# SCH_-_Peripheral.net
KiCad netlist of a schematic drawn in Altium Designer
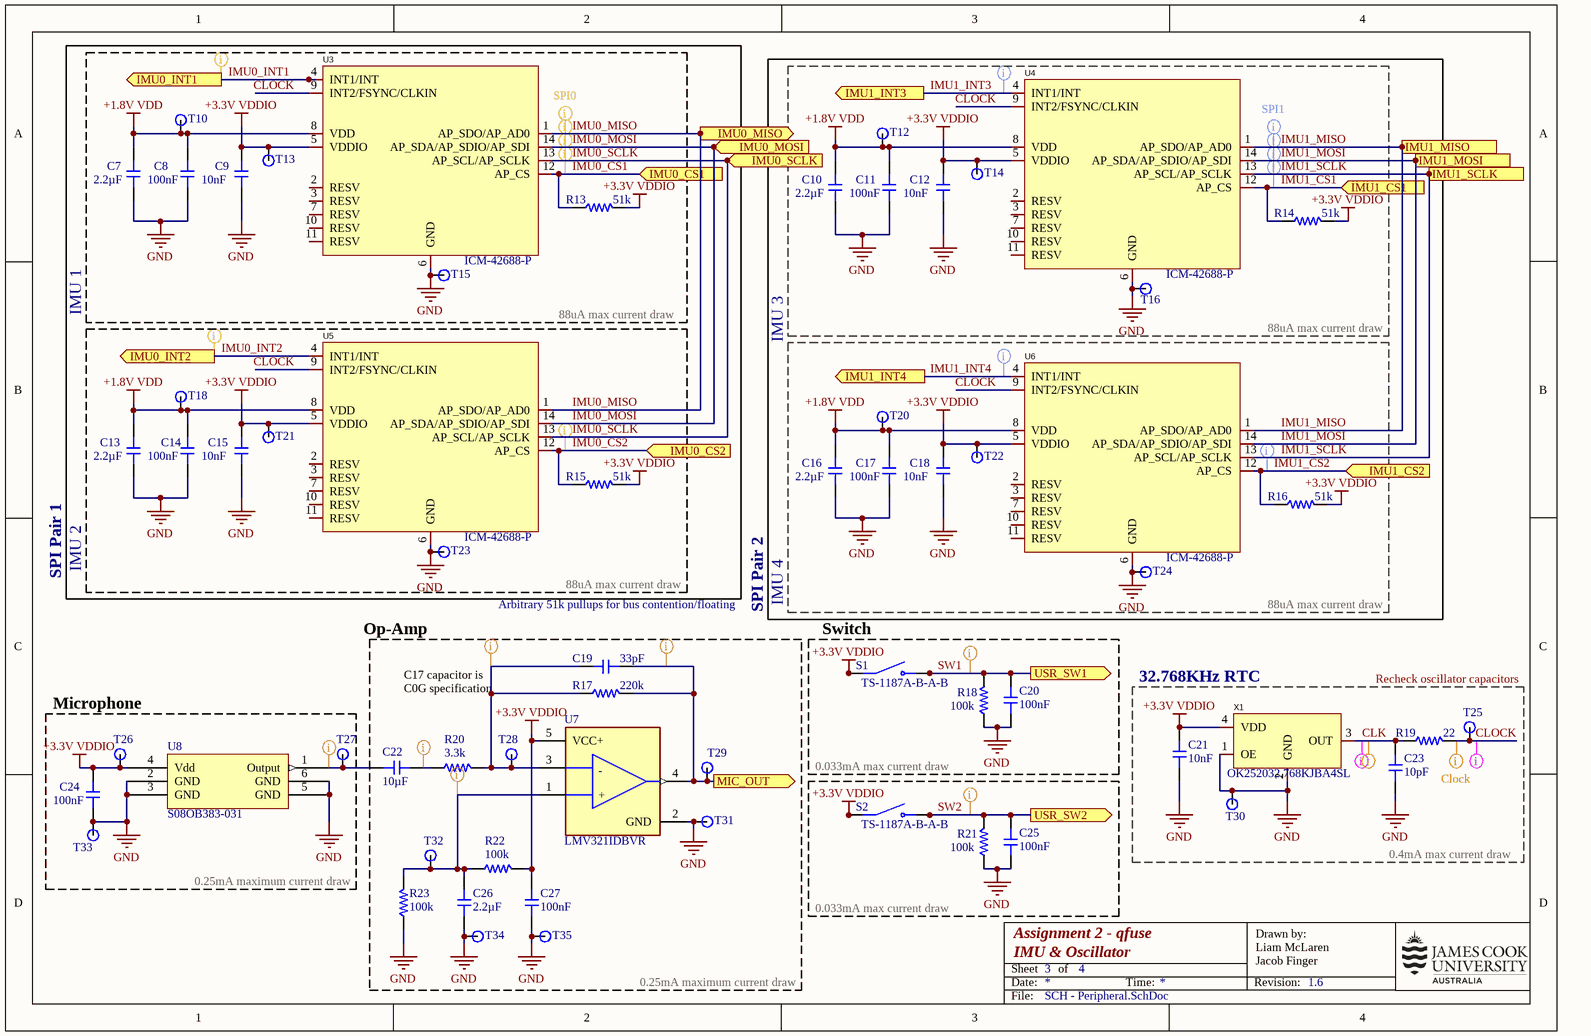
[diagram p0: SCH - Peripheral.SchDoc]

(export (version "E")
  (design (tool "Eeschema 10.0.6"))
  (components
    (comp (ref "C7")
      (value "2.2µF")
      (footprint "CAP-0402")
      (description "Capacitor, Ceramic (MLCC), 2.2uF, ±20%, 6.3V, X5R, ±20%, SMD 0402")
      (fields (field (name "TOLERANCE") "20%") (field (name "JLCPCB PART NUMBER") "C12530"))
      (libsource (lib "Finmac Systems") (part "GRM21BR61H106KE43L"))
    )
    (comp (ref "C8")
      (value "100nF")
      (footprint "CAP-0402")
      (description "Capacitor, Ceramic (MLCC), 100nF, ±10%, 50V, X7R, ±10%, SMD 0402")
      (fields (field (name "JLCPCB PART NUMBER") "C307331") (field (name "JLCPCB BASIC PART") "Yes"))
      (libsource (lib "Finmac Systems") (part "GRM21BR61H106KE43L"))
    )
    (comp (ref "C9")
      (value "10nF")
      (footprint "CAP-0402")
      (description "Capacitor, Ceramic (MLCC), 10nF, ±10%, 50V, X7R, ±10%, SMD 0402")
      (fields
        (field (name "JLCPCB PART NUMBER") "C15195")
        (field (name "MANUFACTURER") "Samsung Electro-Mechanics")
      )
      (libsource (lib "Finmac Systems") (part "GRM21BR61H106KE43L"))
    )
    (comp (ref "C10")
      (value "2.2µF")
      (footprint "CAP-0402")
      (description "Capacitor, Ceramic (MLCC), 2.2uF, ±20%, 6.3V, X5R, ±20%, SMD 0402")
      (fields (field (name "TOLERANCE") "20%") (field (name "JLCPCB PART NUMBER") "C12530"))
      (libsource (lib "Finmac Systems") (part "GRM21BR61H106KE43L"))
    )
    (comp (ref "C11")
      (value "100nF")
      (footprint "CAP-0402")
      (description "Capacitor, Ceramic (MLCC), 100nF, ±10%, 50V, X7R, ±10%, SMD 0402")
      (fields (field (name "JLCPCB PART NUMBER") "C307331") (field (name "JLCPCB BASIC PART") "Yes"))
      (libsource (lib "Finmac Systems") (part "GRM21BR61H106KE43L"))
    )
    (comp (ref "C12")
      (value "10nF")
      (footprint "CAP-0402")
      (description "Capacitor, Ceramic (MLCC), 10nF, ±10%, 50V, X7R, ±10%, SMD 0402")
      (fields
        (field (name "JLCPCB PART NUMBER") "C15195")
        (field (name "MANUFACTURER") "Samsung Electro-Mechanics")
      )
      (libsource (lib "Finmac Systems") (part "GRM21BR61H106KE43L"))
    )
    (comp (ref "C13")
      (value "2.2µF")
      (footprint "CAP-0402")
      (description "Capacitor, Ceramic (MLCC), 2.2uF, ±20%, 6.3V, X5R, ±20%, SMD 0402")
      (fields (field (name "TOLERANCE") "20%") (field (name "JLCPCB PART NUMBER") "C12530"))
      (libsource (lib "Finmac Systems") (part "GRM21BR61H106KE43L"))
    )
    (comp (ref "C14")
      (value "100nF")
      (footprint "CAP-0402")
      (description "Capacitor, Ceramic (MLCC), 100nF, ±10%, 50V, X7R, ±10%, SMD 0402")
      (fields (field (name "JLCPCB PART NUMBER") "C307331") (field (name "JLCPCB BASIC PART") "Yes"))
      (libsource (lib "Finmac Systems") (part "GRM21BR61H106KE43L"))
    )
    (comp (ref "C15")
      (value "10nF")
      (footprint "CAP-0402")
      (description "Capacitor, Ceramic (MLCC), 10nF, ±10%, 50V, X7R, ±10%, SMD 0402")
      (fields
        (field (name "JLCPCB PART NUMBER") "C15195")
        (field (name "MANUFACTURER") "Samsung Electro-Mechanics")
      )
      (libsource (lib "Finmac Systems") (part "GRM21BR61H106KE43L"))
    )
    (comp (ref "C16")
      (value "2.2µF")
      (footprint "CAP-0402")
      (description "Capacitor, Ceramic (MLCC), 2.2uF, ±20%, 6.3V, X5R, ±20%, SMD 0402")
      (fields (field (name "TOLERANCE") "20%") (field (name "JLCPCB PART NUMBER") "C12530"))
      (libsource (lib "Finmac Systems") (part "GRM21BR61H106KE43L"))
    )
    (comp (ref "C17")
      (value "100nF")
      (footprint "CAP-0402")
      (description "Capacitor, Ceramic (MLCC), 100nF, ±10%, 50V, X7R, ±10%, SMD 0402")
      (fields (field (name "JLCPCB PART NUMBER") "C307331") (field (name "JLCPCB BASIC PART") "Yes"))
      (libsource (lib "Finmac Systems") (part "GRM21BR61H106KE43L"))
    )
    (comp (ref "C18")
      (value "10nF")
      (footprint "CAP-0402")
      (description "Capacitor, Ceramic (MLCC), 10nF, ±10%, 50V, X7R, ±10%, SMD 0402")
      (fields
        (field (name "JLCPCB PART NUMBER") "C15195")
        (field (name "MANUFACTURER") "Samsung Electro-Mechanics")
      )
      (libsource (lib "Finmac Systems") (part "GRM21BR61H106KE43L"))
    )
    (comp (ref "C19")
      (value "33pF")
      (footprint "CAP-0402")
      (description "Capacitor, Ceramic (MLCC), 33pF, ±5%, 50V, C0G, ±5%, SMD 0402")
      (fields (field (name "TOLERANCE") "5%") (field (name "MANUFACTURER PART NUMBER") "0402CG330J500NT"))
      (libsource (lib "Finmac Systems") (part "GRM21BR61H106KE43L"))
    )
    (comp (ref "C20")
      (value "100nF")
      (footprint "CAP-0402")
      (description "Capacitor, Ceramic (MLCC), 100nF, ±10%, 16V, X7R, ±10%, SMD 0402")
      (fields
        (field (name "MANUFACTURER PART NUMBER") "CL05B104KO5NNNC")
        (field (name "MANUFACTURER") "Samsung Electro-Mechanics")
      )
      (libsource (lib "Finmac Systems") (part "GRM21BR61H106KE43L"))
    )
    (comp (ref "C21")
      (value "10nF")
      (footprint "CAP-0402")
      (description "Capacitor, Ceramic (MLCC), 10nF, ±10%, 50V, X7R, ±10%, SMD 0402")
      (fields
        (field (name "JLCPCB PART NUMBER") "C15195")
        (field (name "MANUFACTURER") "Samsung Electro-Mechanics")
      )
      (libsource (lib "Finmac Systems") (part "GRM21BR61H106KE43L"))
    )
    (comp (ref "C22")
      (value "10µF")
      (footprint "CAP-0402")
      (description "Capacitor, Ceramic (MLCC), 10uF, ±20%, 6.3V, X5R, ±20%, SMD 0402")
      (fields
        (field (name "MANUFACTURER") "Samsung Electro-Mechanics")
        (field (name "JLCPCB PART NUMBER") "C15525")
      )
      (libsource (lib "Finmac Systems") (part "GRM21BR61H106KE43L"))
    )
    (comp (ref "C23")
      (value "10pF")
      (footprint "CAP-0402")
      (description "Capacitor, Ceramic (MLCC), 10pF, ±5%, 50V, C0G, ±5%, SMD 0402")
      (fields
        (field (name "MANUFACTURER") "Samsung Electro-Mechanics")
        (field (name "JLCPCB PART NUMBER") "C32949")
      )
      (libsource (lib "Finmac Systems") (part "GRM21BR61H106KE43L"))
    )
    (comp (ref "C24")
      (value "100nF")
      (footprint "CAP-0402")
      (description "Capacitor, Ceramic (MLCC), 100nF, ±10%, 50V, X7R, ±10%, SMD 0402")
      (fields
        (field (name "MANUFACTURER PART NUMBER") "CL05B104KB54PNC")
        (field (name "MANUFACTURER") "Samsung Electro-Mechanics")
      )
      (libsource (lib "Finmac Systems") (part "GRM21BR61H106KE43L"))
    )
    (comp (ref "C25")
      (value "100nF")
      (footprint "CAP-0402")
      (description "Capacitor, Ceramic (MLCC), 100nF, ±10%, 16V, X7R, ±10%, SMD 0402")
      (fields
        (field (name "MANUFACTURER PART NUMBER") "CL05B104KO5NNNC")
        (field (name "MANUFACTURER") "Samsung Electro-Mechanics")
      )
      (libsource (lib "Finmac Systems") (part "GRM21BR61H106KE43L"))
    )
    (comp (ref "C26")
      (value "2.2µF")
      (footprint "CAP-0402")
      (description "Capacitor, Ceramic (MLCC), 2.2uF, ±20%, 6.3V, X5R, ±20%, SMD 0402")
      (fields
        (field (name "MANUFACTURER PART NUMBER") "CL05A225MQ5NSNC")
        (field (name "MANUFACTURER") "Samsung Electro-Mechanics")
      )
      (libsource (lib "Finmac Systems") (part "GRM21BR61H106KE43L"))
    )
    (comp (ref "C27")
      (value "100nF")
      (footprint "CAP-0402")
      (description "Capacitor, Ceramic (MLCC), 100nF, ±10%, 50V, X7R, ±10%, SMD 0402")
      (fields
        (field (name "MANUFACTURER PART NUMBER") "CL05B104KB54PNC")
        (field (name "MANUFACTURER") "Samsung Electro-Mechanics")
      )
      (libsource (lib "Finmac Systems") (part "GRM21BR61H106KE43L"))
    )
    (comp (ref "R13")
      (value "51k")
      (footprint "RES-0402")
      (description "Resistor, 51kΩ, ±1%, 62.5mW, 50V, ±100ppm/℃, -55℃~+155℃, SMD 0402")
      (fields
        (field (name "JLCPCB PART NUMBER") "C25794")
        (field (name "MANUFACTURER PART NUMBER") "0402WGF5102TCE")
      )
      (libsource (lib "Finmac Systems") (part "1206W4F7500T5E"))
    )
    (comp (ref "R14")
      (value "51k")
      (footprint "RES-0402")
      (description "Resistor, 51kΩ, ±1%, 62.5mW, 50V, ±100ppm/℃, -55℃~+155℃, SMD 0402")
      (fields
        (field (name "JLCPCB PART NUMBER") "C25794")
        (field (name "MANUFACTURER PART NUMBER") "0402WGF5102TCE")
      )
      (libsource (lib "Finmac Systems") (part "1206W4F7500T5E"))
    )
    (comp (ref "R15")
      (value "51k")
      (footprint "RES-0402")
      (description "Resistor, 51kΩ, ±1%, 62.5mW, 50V, ±100ppm/℃, -55℃~+155℃, SMD 0402")
      (fields
        (field (name "JLCPCB PART NUMBER") "C25794")
        (field (name "MANUFACTURER PART NUMBER") "0402WGF5102TCE")
      )
      (libsource (lib "Finmac Systems") (part "1206W4F7500T5E"))
    )
    (comp (ref "R16")
      (value "51k")
      (footprint "RES-0402")
      (description "Resistor, 51kΩ, ±1%, 62.5mW, 50V, ±100ppm/℃, -55℃~+155℃, SMD 0402")
      (fields
        (field (name "JLCPCB PART NUMBER") "C25794")
        (field (name "MANUFACTURER PART NUMBER") "0402WGF5102TCE")
      )
      (libsource (lib "Finmac Systems") (part "1206W4F7500T5E"))
    )
    (comp (ref "R17")
      (value "220k")
      (footprint "RES-0603")
      (description "Resistor, 220kΩ, ±1%, 100mW, 75V, ±100ppm/℃, -55℃~+155℃, SMD 0603")
      (fields (field (name "TOLERANCE") "1%") (field (name "MANUFACTURER PART NUMBER") "0603WAF2203T5E"))
      (libsource (lib "Finmac Systems") (part "1206W4F7500T5E"))
    )
    (comp (ref "R18")
      (value "100k")
      (footprint "RES-0402")
      (description "Resistor, 100kΩ, ±1%, 62.5mW, 50V, ±100ppm/℃, -55℃~+155℃, SMD 0402")
      (fields (field (name "TOLERANCE") "1%") (field (name "MANUFACTURER") "Uniroyal"))
      (libsource (lib "Finmac Systems") (part "1206W4F7500T5E"))
    )
    (comp (ref "R19")
      (value "22")
      (footprint "RES-0402")
      (description "Resistor, 22Ω, ±1%, 62.5mW, 50V, ±200ppm/℃, -55℃~+155℃, SMD 0402")
      (fields
        (field (name "MANUFACTURER PART NUMBER") "0402WGF220JTCE")
        (field (name "JLCPCB PART NUMBER") "C25092")
      )
      (libsource (lib "Finmac Systems") (part "1206W4F7500T5E"))
    )
    (comp (ref "R20")
      (value "3.3k")
      (footprint "RES-0402")
      (description "Resistor, 3.3kΩ, ±1%, 62.5mW, 50V, ±100ppm/℃, -55℃~+155℃, SMD 0402")
      (fields (field (name "JLCPCB PART NUMBER") "C25890") (field (name "MANUFACTURER") "Uniroyal"))
      (libsource (lib "Finmac Systems") (part "1206W4F7500T5E"))
    )
    (comp (ref "R21")
      (value "100k")
      (footprint "RES-0402")
      (description "Resistor, 100kΩ, ±1%, 62.5mW, 50V, ±100ppm/℃, -55℃~+155℃, SMD 0402")
      (fields (field (name "TOLERANCE") "1%") (field (name "MANUFACTURER") "Uniroyal"))
      (libsource (lib "Finmac Systems") (part "1206W4F7500T5E"))
    )
    (comp (ref "R22")
      (value "100k")
      (footprint "RES-0402")
      (description "Resistor, 100kΩ, ±1%, 62.5mW, 50V, ±100ppm/℃, -55℃~+155℃, SMD 0402")
      (fields (field (name "TOLERANCE") "1%") (field (name "MANUFACTURER") "Uniroyal"))
      (libsource (lib "Finmac Systems") (part "1206W4F7500T5E"))
    )
    (comp (ref "R23")
      (value "100k")
      (footprint "RES-0402")
      (description "Resistor, 100kΩ, ±1%, 62.5mW, 50V, ±100ppm/℃, -55℃~+155℃, SMD 0402")
      (fields (field (name "TOLERANCE") "1%") (field (name "MANUFACTURER") "Uniroyal"))
      (libsource (lib "Finmac Systems") (part "1206W4F7500T5E"))
    )
    (comp (ref "S1")
      (value "TS-1187A-B-A-B")
      (footprint "SW_TS-1187A-B-A-B")
      (description "SPST 50mA @ 12VDC Top Actuated Round Button 160gf SMD Tactile Switches RoHS")
      (fields (field (name "JLCPCB PART NUMBER") "C318884"))
      (libsource (lib "qfuse_sch_lib") (part "CMP-051-000000-5"))
    )
    (comp (ref "S2")
      (value "TS-1187A-B-A-B")
      (footprint "SW_TS-1187A-B-A-B")
      (description "SPST 50mA @ 12VDC Top Actuated Round Button 160gf SMD Tactile Switches RoHS")
      (fields (field (name "JLCPCB PART NUMBER") "C318884"))
      (libsource (lib "qfuse_sch_lib") (part "CMP-051-000000-5"))
    )
    (comp (ref "T10")
      (value "TP")
      (footprint "TestPoint")
      (libsource (lib "DatumPenLibrary") (part "TestPoint"))
    )
    (comp (ref "T12")
      (value "TP")
      (footprint "TestPoint")
      (libsource (lib "DatumPenLibrary") (part "TestPoint"))
    )
    (comp (ref "T13")
      (value "TP")
      (footprint "TestPoint")
      (libsource (lib "DatumPenLibrary") (part "TestPoint"))
    )
    (comp (ref "T14")
      (value "TP")
      (footprint "TestPoint")
      (libsource (lib "DatumPenLibrary") (part "TestPoint"))
    )
    (comp (ref "T15")
      (value "TP")
      (footprint "TestPoint")
      (libsource (lib "DatumPenLibrary") (part "TestPoint"))
    )
    (comp (ref "T16")
      (value "TP")
      (footprint "TestPoint")
      (libsource (lib "DatumPenLibrary") (part "TestPoint"))
    )
    (comp (ref "T18")
      (value "TP")
      (footprint "TestPoint")
      (libsource (lib "DatumPenLibrary") (part "TestPoint"))
    )
    (comp (ref "T20")
      (value "TP")
      (footprint "TestPoint")
      (libsource (lib "DatumPenLibrary") (part "TestPoint"))
    )
    (comp (ref "T21")
      (value "TP")
      (footprint "TestPoint")
      (libsource (lib "DatumPenLibrary") (part "TestPoint"))
    )
    (comp (ref "T22")
      (value "TP")
      (footprint "TestPoint")
      (libsource (lib "DatumPenLibrary") (part "TestPoint"))
    )
    (comp (ref "T23")
      (value "TP")
      (footprint "TestPoint")
      (libsource (lib "DatumPenLibrary") (part "TestPoint"))
    )
    (comp (ref "T24")
      (value "TP")
      (footprint "TestPoint")
      (libsource (lib "DatumPenLibrary") (part "TestPoint"))
    )
    (comp (ref "T25")
      (value "TP")
      (footprint "TestPoint")
      (libsource (lib "DatumPenLibrary") (part "TestPoint"))
    )
    (comp (ref "T26")
      (value "TP")
      (footprint "TestPoint")
      (libsource (lib "DatumPenLibrary") (part "TestPoint"))
    )
    (comp (ref "T27")
      (value "TP")
      (footprint "TestPoint")
      (libsource (lib "DatumPenLibrary") (part "TestPoint"))
    )
    (comp (ref "T28")
      (value "TP")
      (footprint "TestPoint")
      (libsource (lib "DatumPenLibrary") (part "TestPoint"))
    )
    (comp (ref "T29")
      (value "TP")
      (footprint "TestPoint")
      (libsource (lib "DatumPenLibrary") (part "TestPoint"))
    )
    (comp (ref "T30")
      (value "TP")
      (footprint "TestPoint")
      (libsource (lib "DatumPenLibrary") (part "TestPoint"))
    )
    (comp (ref "T31")
      (value "TP")
      (footprint "TestPoint")
      (libsource (lib "DatumPenLibrary") (part "TestPoint"))
    )
    (comp (ref "T32")
      (value "TP")
      (footprint "TestPoint")
      (libsource (lib "DatumPenLibrary") (part "TestPoint"))
    )
    (comp (ref "T33")
      (value "TP")
      (footprint "TestPoint")
      (libsource (lib "DatumPenLibrary") (part "TestPoint"))
    )
    (comp (ref "T34")
      (value "TP")
      (footprint "TestPoint")
      (libsource (lib "DatumPenLibrary") (part "TestPoint"))
    )
    (comp (ref "T35")
      (value "TP")
      (footprint "TestPoint")
      (libsource (lib "DatumPenLibrary") (part "TestPoint"))
    )
    (comp (ref "U3")
      (value "ICM-42688-P")
      (footprint "LGA-14_L3.0-W2.5-P0.50-TL")
      (description "ICM-42688-P LGA-14(2.5x3) Attitude Sensor/Gyroscope")
      (fields (field (name "MANUFACTURER") "TDK InvenSense(应美盛)") (field (name "LCSC PART #") "C1850418"))
      (libsource (lib "qfuse_sch_lib") (part "ICM-42688-P"))
    )
    (comp (ref "U4")
      (value "ICM-42688-P")
      (footprint "LGA-14_L3.0-W2.5-P0.50-TL")
      (description "ICM-42688-P LGA-14(2.5x3) Attitude Sensor/Gyroscope")
      (fields (field (name "MANUFACTURER") "TDK InvenSense(应美盛)") (field (name "LCSC PART #") "C1850418"))
      (libsource (lib "qfuse_sch_lib") (part "ICM-42688-P"))
    )
    (comp (ref "U5")
      (value "ICM-42688-P")
      (footprint "LGA-14_L3.0-W2.5-P0.50-TL")
      (description "ICM-42688-P LGA-14(2.5x3) Attitude Sensor/Gyroscope")
      (fields (field (name "MANUFACTURER") "TDK InvenSense(应美盛)") (field (name "LCSC PART #") "C1850418"))
      (libsource (lib "qfuse_sch_lib") (part "ICM-42688-P"))
    )
    (comp (ref "U6")
      (value "ICM-42688-P")
      (footprint "LGA-14_L3.0-W2.5-P0.50-TL")
      (description "ICM-42688-P LGA-14(2.5x3) Attitude Sensor/Gyroscope")
      (fields (field (name "MANUFACTURER") "TDK InvenSense(应美盛)") (field (name "LCSC PART #") "C1850418"))
      (libsource (lib "qfuse_sch_lib") (part "ICM-42688-P"))
    )
    (comp (ref "U7")
      (value "LMV321IDBVR")
      (footprint "FP-DBV0005A-MFG")
      (description "General Purpose Amplifier 1 Circuit Rail-to-Rail SOT-23-5")
      (fields (field (name "JLCPCB PART NUMBER") "C7972"))
      (libsource (lib "qfuse_sch_lib") (part "CMP-00012-2"))
    )
    (comp (ref "U8")
      (value "S08OB383-031")
      (footprint "Goertek_S08OB381-026")
      (description "MEMS Microphone SMD 3.76x3x1.1mm")
      (fields (field (name "JLCPCB PART NUMBER") "C233789"))
      (libsource (lib "qfuse_sch_lib") (part "CMP-00027-00000-1"))
    )
    (comp (ref "X1")
      (value "OK252032.768KJBA4SL")
      (footprint "OSC-SMD_4P-L2.5-W2.0-BL")
      (fields (field (name "MANUFACTURER") "HELE(台湾加高)") (field (name "LCSC PART #") "C669098"))
      (libsource (lib "qfuse_sch_lib") (part "OK252032.768KJBA4SL"))
    )
  )
  (nets
    (net (code "1") (name "+1.8V VDD") (class "Default")
      (node (ref "C10") (pin "2") (pinfunction "2_2") (pintype "passive"))
      (node (ref "C11") (pin "2") (pinfunction "2_2") (pintype "passive"))
      (node (ref "C13") (pin "2") (pinfunction "2_2") (pintype "passive"))
      (node (ref "C14") (pin "2") (pinfunction "2_2") (pintype "passive"))
      (node (ref "C16") (pin "2") (pinfunction "2_2") (pintype "passive"))
      (node (ref "C17") (pin "2") (pinfunction "2_2") (pintype "passive"))
      (node (ref "C7") (pin "2") (pinfunction "2_2") (pintype "passive"))
      (node (ref "C8") (pin "2") (pinfunction "2_2") (pintype "passive"))
      (node (ref "T10") (pin "1") (pinfunction "TP_1") (pintype "passive"))
      (node (ref "T12") (pin "1") (pinfunction "TP_1") (pintype "passive"))
      (node (ref "T18") (pin "1") (pinfunction "TP_1") (pintype "passive"))
      (node (ref "T20") (pin "1") (pinfunction "TP_1") (pintype "passive"))
      (node (ref "U3") (pin "8") (pinfunction "VDD_8") (pintype "passive"))
      (node (ref "U4") (pin "8") (pinfunction "VDD_8") (pintype "passive"))
      (node (ref "U5") (pin "8") (pinfunction "VDD_8") (pintype "passive"))
      (node (ref "U6") (pin "8") (pinfunction "VDD_8") (pintype "passive"))
    )
    (net (code "2") (name "+3.3V VDDIO") (class "Default")
      (node (ref "C12") (pin "2") (pinfunction "2_2") (pintype "passive"))
      (node (ref "C15") (pin "2") (pinfunction "2_2") (pintype "passive"))
      (node (ref "C18") (pin "2") (pinfunction "2_2") (pintype "passive"))
      (node (ref "C21") (pin "2") (pinfunction "2_2") (pintype "passive"))
      (node (ref "C24") (pin "2") (pinfunction "2_2") (pintype "passive"))
      (node (ref "C27") (pin "2") (pinfunction "2_2") (pintype "passive"))
      (node (ref "C9") (pin "2") (pinfunction "2_2") (pintype "passive"))
      (node (ref "R13") (pin "2") (pinfunction "2_2") (pintype "passive"))
      (node (ref "R14") (pin "2") (pinfunction "2_2") (pintype "passive"))
      (node (ref "R15") (pin "2") (pinfunction "2_2") (pintype "passive"))
      (node (ref "R16") (pin "2") (pinfunction "2_2") (pintype "passive"))
      (node (ref "R22") (pin "2") (pinfunction "2_2") (pintype "passive"))
      (node (ref "S1") (pin "A") (pinfunction "COM_A") (pintype "passive"))
      (node (ref "S1") (pin "B") (pinfunction "COM_B") (pintype "passive"))
      (node (ref "S2") (pin "A") (pinfunction "COM_A") (pintype "passive"))
      (node (ref "S2") (pin "B") (pinfunction "COM_B") (pintype "passive"))
      (node (ref "T13") (pin "1") (pinfunction "TP_1") (pintype "passive"))
      (node (ref "T14") (pin "1") (pinfunction "TP_1") (pintype "passive"))
      (node (ref "T21") (pin "1") (pinfunction "TP_1") (pintype "passive"))
      (node (ref "T22") (pin "1") (pinfunction "TP_1") (pintype "passive"))
      (node (ref "T26") (pin "1") (pinfunction "TP_1") (pintype "passive"))
      (node (ref "U3") (pin "5") (pinfunction "VDDIO_5") (pintype "passive"))
      (node (ref "U4") (pin "5") (pinfunction "VDDIO_5") (pintype "passive"))
      (node (ref "U5") (pin "5") (pinfunction "VDDIO_5") (pintype "passive"))
      (node (ref "U6") (pin "5") (pinfunction "VDDIO_5") (pintype "passive"))
      (node (ref "U7") (pin "5") (pinfunction "VCC+_5") (pintype "power_in"))
      (node (ref "U8") (pin "4") (pinfunction "Vdd_4") (pintype "power_in"))
      (node (ref "X1") (pin "4") (pinfunction "VDD_4") (pintype "passive"))
    )
    (net (code "3") (name "/CLK") (class "Default")
      (node (ref "C23") (pin "2") (pinfunction "2_2") (pintype "passive"))
      (node (ref "R19") (pin "1") (pinfunction "1_1") (pintype "passive"))
      (node (ref "X1") (pin "3") (pinfunction "OUT_3") (pintype "passive"))
    )
    (net (code "4") (name "/CLOCK") (class "Default")
      (node (ref "R19") (pin "2") (pinfunction "2_2") (pintype "passive"))
      (node (ref "T25") (pin "1") (pinfunction "TP_1") (pintype "passive"))
      (node (ref "U3") (pin "9") (pinfunction "INT2/FSYNC/CLKIN_9") (pintype "passive"))
      (node (ref "U4") (pin "9") (pinfunction "INT2/FSYNC/CLKIN_9") (pintype "passive"))
      (node (ref "U5") (pin "9") (pinfunction "INT2/FSYNC/CLKIN_9") (pintype "passive"))
      (node (ref "U6") (pin "9") (pinfunction "INT2/FSYNC/CLKIN_9") (pintype "passive"))
    )
    (net (code "5") (name "/IMU0_CS1") (class "Default")
      (node (ref "R13") (pin "1") (pinfunction "1_1") (pintype "passive"))
      (node (ref "U3") (pin "12") (pinfunction "AP_CS_12") (pintype "passive"))
    )
    (net (code "6") (name "/IMU0_CS2") (class "Default")
      (node (ref "R15") (pin "1") (pinfunction "1_1") (pintype "passive"))
      (node (ref "U5") (pin "12") (pinfunction "AP_CS_12") (pintype "passive"))
    )
    (net (code "7") (name "/IMU0_INT1") (class "Default")
      (node (ref "U3") (pin "4") (pinfunction "INT1/INT_4") (pintype "passive"))
    )
    (net (code "8") (name "/IMU0_INT2") (class "Default")
      (node (ref "U5") (pin "4") (pinfunction "INT1/INT_4") (pintype "passive"))
    )
    (net (code "9") (name "/IMU0_MISO") (class "Default")
      (node (ref "U3") (pin "1") (pinfunction "AP_SDO/AP_AD0_1") (pintype "passive"))
      (node (ref "U5") (pin "1") (pinfunction "AP_SDO/AP_AD0_1") (pintype "passive"))
    )
    (net (code "10") (name "/IMU0_MOSI") (class "Default")
      (node (ref "U3") (pin "14") (pinfunction "AP_SDA/AP_SDIO/AP_SDI_14") (pintype "passive"))
      (node (ref "U5") (pin "14") (pinfunction "AP_SDA/AP_SDIO/AP_SDI_14") (pintype "passive"))
    )
    (net (code "11") (name "/IMU0_SCLK") (class "Default")
      (node (ref "U3") (pin "13") (pinfunction "AP_SCL/AP_SCLK_13") (pintype "passive"))
      (node (ref "U5") (pin "13") (pinfunction "AP_SCL/AP_SCLK_13") (pintype "passive"))
    )
    (net (code "12") (name "/IMU1_CS1") (class "Default")
      (node (ref "R14") (pin "1") (pinfunction "1_1") (pintype "passive"))
      (node (ref "U4") (pin "12") (pinfunction "AP_CS_12") (pintype "passive"))
    )
    (net (code "13") (name "/IMU1_CS2") (class "Default")
      (node (ref "R16") (pin "1") (pinfunction "1_1") (pintype "passive"))
      (node (ref "U6") (pin "12") (pinfunction "AP_CS_12") (pintype "passive"))
    )
    (net (code "14") (name "/IMU1_INT3") (class "Default")
      (node (ref "U4") (pin "4") (pinfunction "INT1/INT_4") (pintype "passive"))
    )
    (net (code "15") (name "/IMU1_INT4") (class "Default")
      (node (ref "U6") (pin "4") (pinfunction "INT1/INT_4") (pintype "passive"))
    )
    (net (code "16") (name "/IMU1_MISO") (class "Default")
      (node (ref "U4") (pin "1") (pinfunction "AP_SDO/AP_AD0_1") (pintype "passive"))
      (node (ref "U6") (pin "1") (pinfunction "AP_SDO/AP_AD0_1") (pintype "passive"))
    )
    (net (code "17") (name "/IMU1_MOSI") (class "Default")
      (node (ref "U4") (pin "14") (pinfunction "AP_SDA/AP_SDIO/AP_SDI_14") (pintype "passive"))
      (node (ref "U6") (pin "14") (pinfunction "AP_SDA/AP_SDIO/AP_SDI_14") (pintype "passive"))
    )
    (net (code "18") (name "/IMU1_SCLK") (class "Default")
      (node (ref "U4") (pin "13") (pinfunction "AP_SCL/AP_SCLK_13") (pintype "passive"))
      (node (ref "U6") (pin "13") (pinfunction "AP_SCL/AP_SCLK_13") (pintype "passive"))
    )
    (net (code "19") (name "/MIC_OUT") (class "Default")
      (node (ref "C19") (pin "2") (pinfunction "2_2") (pintype "passive"))
      (node (ref "R17") (pin "2") (pinfunction "2_2") (pintype "passive"))
      (node (ref "T29") (pin "1") (pinfunction "TP_1") (pintype "passive"))
      (node (ref "U7") (pin "4") (pinfunction "OUT_4") (pintype "output"))
    )
    (net (code "20") (name "/SW1") (class "Default")
      (node (ref "C20") (pin "2") (pinfunction "2_2") (pintype "passive"))
      (node (ref "R18") (pin "2") (pinfunction "2_2") (pintype "passive"))
      (node (ref "S1") (pin "C") (pinfunction "NO_C") (pintype "passive"))
      (node (ref "S1") (pin "D") (pinfunction "NO_D") (pintype "passive"))
    )
    (net (code "21") (name "/SW2") (class "Default")
      (node (ref "C25") (pin "2") (pinfunction "2_2") (pintype "passive"))
      (node (ref "R21") (pin "2") (pinfunction "2_2") (pintype "passive"))
      (node (ref "S2") (pin "C") (pinfunction "NO_C") (pintype "passive"))
      (node (ref "S2") (pin "D") (pinfunction "NO_D") (pintype "passive"))
    )
    (net (code "22") (name "GND") (class "Default")
      (node (ref "C10") (pin "1") (pinfunction "1_1") (pintype "passive"))
      (node (ref "C11") (pin "1") (pinfunction "1_1") (pintype "passive"))
      (node (ref "C12") (pin "1") (pinfunction "1_1") (pintype "passive"))
      (node (ref "C13") (pin "1") (pinfunction "1_1") (pintype "passive"))
      (node (ref "C14") (pin "1") (pinfunction "1_1") (pintype "passive"))
      (node (ref "C15") (pin "1") (pinfunction "1_1") (pintype "passive"))
      (node (ref "C16") (pin "1") (pinfunction "1_1") (pintype "passive"))
      (node (ref "C17") (pin "1") (pinfunction "1_1") (pintype "passive"))
      (node (ref "C18") (pin "1") (pinfunction "1_1") (pintype "passive"))
      (node (ref "C20") (pin "1") (pinfunction "1_1") (pintype "passive"))
      (node (ref "C21") (pin "1") (pinfunction "1_1") (pintype "passive"))
      (node (ref "C23") (pin "1") (pinfunction "1_1") (pintype "passive"))
      (node (ref "C24") (pin "1") (pinfunction "1_1") (pintype "passive"))
      (node (ref "C25") (pin "1") (pinfunction "1_1") (pintype "passive"))
      (node (ref "C26") (pin "1") (pinfunction "1_1") (pintype "passive"))
      (node (ref "C27") (pin "1") (pinfunction "1_1") (pintype "passive"))
      (node (ref "C7") (pin "1") (pinfunction "1_1") (pintype "passive"))
      (node (ref "C8") (pin "1") (pinfunction "1_1") (pintype "passive"))
      (node (ref "C9") (pin "1") (pinfunction "1_1") (pintype "passive"))
      (node (ref "R18") (pin "1") (pinfunction "1_1") (pintype "passive"))
      (node (ref "R21") (pin "1") (pinfunction "1_1") (pintype "passive"))
      (node (ref "R23") (pin "1") (pinfunction "1_1") (pintype "passive"))
      (node (ref "T15") (pin "1") (pinfunction "TP_1") (pintype "passive"))
      (node (ref "T16") (pin "1") (pinfunction "TP_1") (pintype "passive"))
      (node (ref "T23") (pin "1") (pinfunction "TP_1") (pintype "passive"))
      (node (ref "T24") (pin "1") (pinfunction "TP_1") (pintype "passive"))
      (node (ref "T30") (pin "1") (pinfunction "TP_1") (pintype "passive"))
      (node (ref "T31") (pin "1") (pinfunction "TP_1") (pintype "passive"))
      (node (ref "T33") (pin "1") (pinfunction "TP_1") (pintype "passive"))
      (node (ref "T34") (pin "1") (pinfunction "TP_1") (pintype "passive"))
      (node (ref "T35") (pin "1") (pinfunction "TP_1") (pintype "passive"))
      (node (ref "U3") (pin "6") (pinfunction "GND_6") (pintype "passive"))
      (node (ref "U4") (pin "6") (pinfunction "GND_6") (pintype "passive"))
      (node (ref "U5") (pin "6") (pinfunction "GND_6") (pintype "passive"))
      (node (ref "U6") (pin "6") (pinfunction "GND_6") (pintype "passive"))
      (node (ref "U7") (pin "2") (pinfunction "GND_2") (pintype "power_in"))
      (node (ref "U8") (pin "2") (pinfunction "GND_2") (pintype "power_in"))
      (node (ref "U8") (pin "3") (pinfunction "GND_3") (pintype "power_in"))
      (node (ref "U8") (pin "5") (pinfunction "GND_5") (pintype "power_in"))
      (node (ref "U8") (pin "6") (pinfunction "GND_6") (pintype "power_in"))
      (node (ref "X1") (pin "1") (pinfunction "OE_1") (pintype "passive"))
      (node (ref "X1") (pin "2") (pinfunction "GND_2") (pintype "passive"))
    )
    (net (code "23") (name "Net-(C22-Pad2)") (class "Default")
      (node (ref "C22") (pin "2") (pinfunction "2_2") (pintype "passive"))
      (node (ref "R20") (pin "1") (pinfunction "1_1") (pintype "passive"))
    )
    (net (code "24") (name "Net-(T27-TP)") (class "Default")
      (node (ref "C22") (pin "1") (pinfunction "1_1") (pintype "passive"))
      (node (ref "T27") (pin "1") (pinfunction "TP_1") (pintype "passive"))
      (node (ref "U8") (pin "1") (pinfunction "Output_1") (pintype "output"))
    )
    (net (code "25") (name "Net-(T28-TP)") (class "Default")
      (node (ref "C19") (pin "1") (pinfunction "1_1") (pintype "passive"))
      (node (ref "R17") (pin "1") (pinfunction "1_1") (pintype "passive"))
      (node (ref "R20") (pin "2") (pinfunction "2_2") (pintype "passive"))
      (node (ref "T28") (pin "1") (pinfunction "TP_1") (pintype "passive"))
      (node (ref "U7") (pin "3") (pinfunction "1IN-_3") (pintype "tri_state"))
    )
    (net (code "26") (name "Net-(T32-TP)") (class "Default")
      (node (ref "C26") (pin "2") (pinfunction "2_2") (pintype "passive"))
      (node (ref "R22") (pin "1") (pinfunction "1_1") (pintype "passive"))
      (node (ref "R23") (pin "2") (pinfunction "2_2") (pintype "passive"))
      (node (ref "T32") (pin "1") (pinfunction "TP_1") (pintype "passive"))
      (node (ref "U7") (pin "1") (pinfunction "1IN+_1") (pintype "tri_state"))
    )
    (net (code "27") (name "unconnected-(U3-RESV-Pad2)") (class "Default")
      (node (ref "U3") (pin "2") (pinfunction "RESV_2") (pintype "passive"))
    )
    (net (code "28") (name "unconnected-(U3-RESV-Pad3)") (class "Default")
      (node (ref "U3") (pin "3") (pinfunction "RESV_3") (pintype "passive"))
    )
    (net (code "29") (name "unconnected-(U3-RESV-Pad7)") (class "Default")
      (node (ref "U3") (pin "7") (pinfunction "RESV_7") (pintype "passive"))
    )
    (net (code "30") (name "unconnected-(U3-RESV-Pad10)") (class "Default")
      (node (ref "U3") (pin "10") (pinfunction "RESV_10") (pintype "passive"))
    )
    (net (code "31") (name "unconnected-(U3-RESV-Pad11)") (class "Default")
      (node (ref "U3") (pin "11") (pinfunction "RESV_11") (pintype "passive"))
    )
    (net (code "32") (name "unconnected-(U4-RESV-Pad2)") (class "Default")
      (node (ref "U4") (pin "2") (pinfunction "RESV_2") (pintype "passive"))
    )
    (net (code "33") (name "unconnected-(U4-RESV-Pad3)") (class "Default")
      (node (ref "U4") (pin "3") (pinfunction "RESV_3") (pintype "passive"))
    )
    (net (code "34") (name "unconnected-(U4-RESV-Pad7)") (class "Default")
      (node (ref "U4") (pin "7") (pinfunction "RESV_7") (pintype "passive"))
    )
    (net (code "35") (name "unconnected-(U4-RESV-Pad10)") (class "Default")
      (node (ref "U4") (pin "10") (pinfunction "RESV_10") (pintype "passive"))
    )
    (net (code "36") (name "unconnected-(U4-RESV-Pad11)") (class "Default")
      (node (ref "U4") (pin "11") (pinfunction "RESV_11") (pintype "passive"))
    )
    (net (code "37") (name "unconnected-(U5-RESV-Pad2)") (class "Default")
      (node (ref "U5") (pin "2") (pinfunction "RESV_2") (pintype "passive"))
    )
    (net (code "38") (name "unconnected-(U5-RESV-Pad3)") (class "Default")
      (node (ref "U5") (pin "3") (pinfunction "RESV_3") (pintype "passive"))
    )
    (net (code "39") (name "unconnected-(U5-RESV-Pad7)") (class "Default")
      (node (ref "U5") (pin "7") (pinfunction "RESV_7") (pintype "passive"))
    )
    (net (code "40") (name "unconnected-(U5-RESV-Pad10)") (class "Default")
      (node (ref "U5") (pin "10") (pinfunction "RESV_10") (pintype "passive"))
    )
    (net (code "41") (name "unconnected-(U5-RESV-Pad11)") (class "Default")
      (node (ref "U5") (pin "11") (pinfunction "RESV_11") (pintype "passive"))
    )
    (net (code "42") (name "unconnected-(U6-RESV-Pad2)") (class "Default")
      (node (ref "U6") (pin "2") (pinfunction "RESV_2") (pintype "passive"))
    )
    (net (code "43") (name "unconnected-(U6-RESV-Pad3)") (class "Default")
      (node (ref "U6") (pin "3") (pinfunction "RESV_3") (pintype "passive"))
    )
    (net (code "44") (name "unconnected-(U6-RESV-Pad7)") (class "Default")
      (node (ref "U6") (pin "7") (pinfunction "RESV_7") (pintype "passive"))
    )
    (net (code "45") (name "unconnected-(U6-RESV-Pad10)") (class "Default")
      (node (ref "U6") (pin "10") (pinfunction "RESV_10") (pintype "passive"))
    )
    (net (code "46") (name "unconnected-(U6-RESV-Pad11)") (class "Default")
      (node (ref "U6") (pin "11") (pinfunction "RESV_11") (pintype "passive"))
    )
  )
)
